# Laser-Battle-IR-Sensor.net
KiCad netlist of a schematic drawn in EAGLE
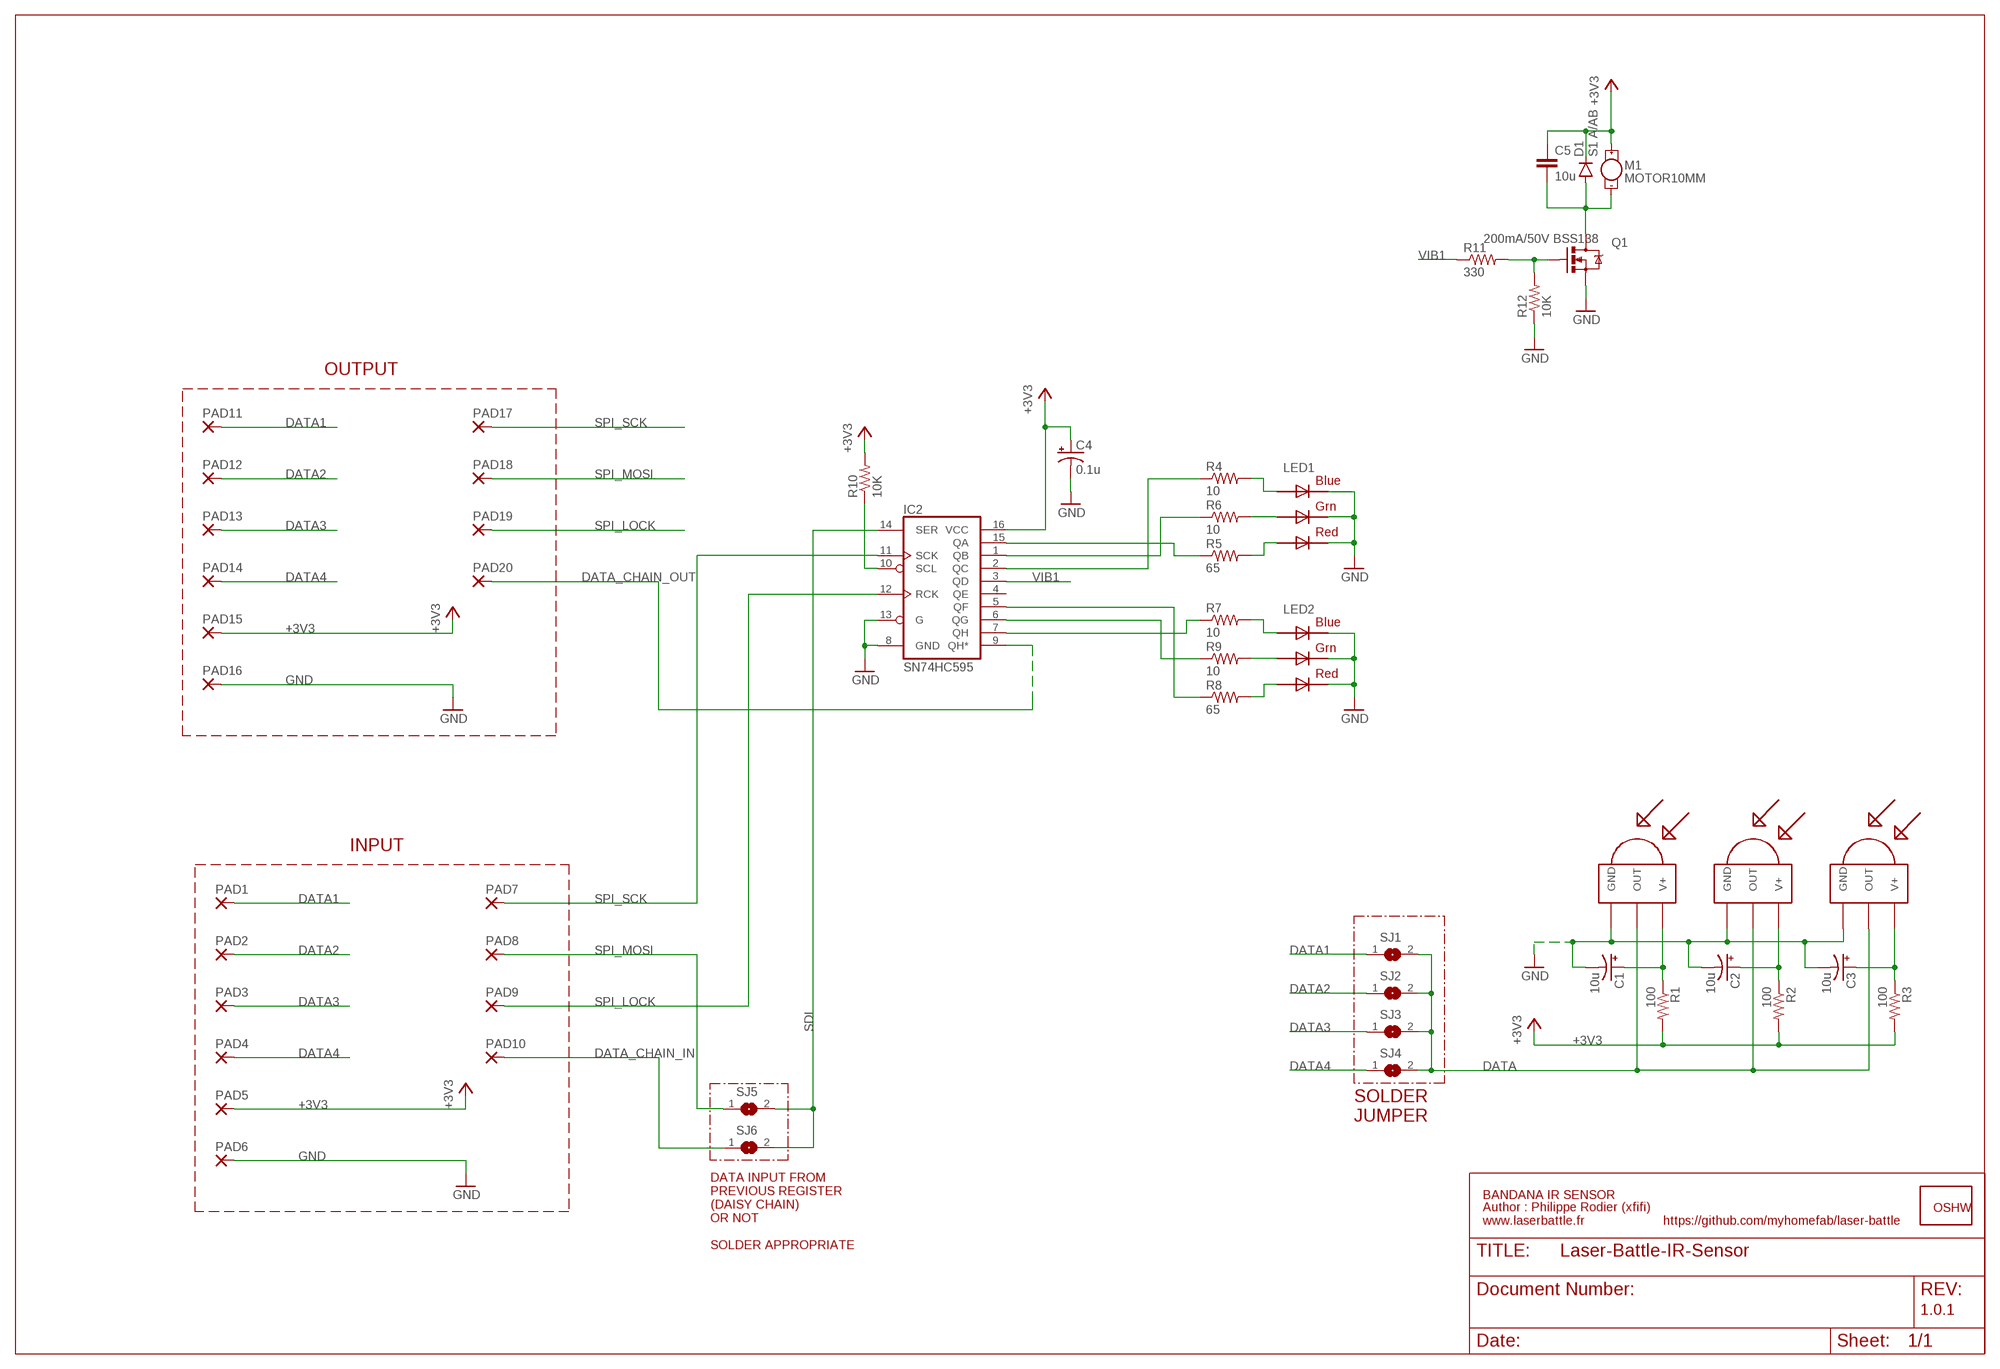
[diagram p0: schematic, sheet 1]

(export (version "E")
  (design (tool "Eeschema 10.0.6"))
  (components
    (comp (ref "C1")
      (value "10u")
      (footprint "eagle-import:EIA3216")
      (libsource (lib "eagle-import") (part "CAP_POL1206"))
    )
    (comp (ref "C2")
      (value "10u")
      (footprint "eagle-import:EIA3216")
      (libsource (lib "eagle-import") (part "CAP_POL1206"))
    )
    (comp (ref "C3")
      (value "10u")
      (footprint "eagle-import:EIA3216")
      (libsource (lib "eagle-import") (part "CAP_POL1206"))
    )
    (comp (ref "C4")
      (value "0.1u")
      (footprint "eagle-import:EIA3216")
      (libsource (lib "eagle-import") (part "CAP_POL1206"))
    )
    (comp (ref "C5")
      (value "10u")
      (footprint "eagle-import:0603-CAP")
      (libsource (lib "eagle-import") (part "CAP0603-CAP"))
    )
    (comp (ref "D1")
      (value "S1 A/AB")
      (footprint "eagle-import:SMA-DIODE")
      (libsource (lib "eagle-import") (part "DIODESMA"))
    )
    (comp (ref "GOLD_ORB_SM1")
      (value "OSHWLOGO_GOLD_ORB_SM")
      (footprint "eagle-import:OSHW2")
      (libsource (lib "eagle-import") (part "OSHWLOGO_GOLD_ORB_SM"))
    )
    (comp (ref "IC2")
      (value "SN74HC595")
      (footprint "eagle-import:TSSOP16")
      (libsource (lib "eagle-import") (part "74595"))
    )
    (comp (ref "IR1")
      (value "TSOP4856")
      (footprint "eagle-import:TSOP18XX")
      (libsource (lib "eagle-import") (part "TSOP4856"))
    )
    (comp (ref "IR2")
      (value "TSOP4856")
      (footprint "eagle-import:TSOP18XX")
      (libsource (lib "eagle-import") (part "TSOP4856"))
    )
    (comp (ref "IR3")
      (value "TSOP4856")
      (footprint "eagle-import:TSOP18XX")
      (libsource (lib "eagle-import") (part "TSOP4856"))
    )
    (comp (ref "LED1")
      (value "RGBLED5050")
      (footprint "eagle-import:RGBLED5050")
      (libsource (lib "eagle-import") (part "RGBLED5050"))
    )
    (comp (ref "LED2")
      (value "RGBLED5050")
      (footprint "eagle-import:RGBLED5050")
      (libsource (lib "eagle-import") (part "RGBLED5050"))
    )
    (comp (ref "M1")
      (value "MOTOR10MM")
      (footprint "eagle-import:VIBE-MOTOR-10MM")
      (libsource (lib "eagle-import") (part "MOTOR10MM"))
    )
    (comp (ref "PAD1")
      (value "1,6/0,8")
      (footprint "eagle-import:1,6_0,8")
      (libsource (lib "eagle-import") (part "1,6/0,8"))
    )
    (comp (ref "PAD2")
      (value "1,6/0,8")
      (footprint "eagle-import:1,6_0,8")
      (libsource (lib "eagle-import") (part "1,6/0,8"))
    )
    (comp (ref "PAD3")
      (value "1,6/0,8")
      (footprint "eagle-import:1,6_0,8")
      (libsource (lib "eagle-import") (part "1,6/0,8"))
    )
    (comp (ref "PAD4")
      (value "1,6/0,8")
      (footprint "eagle-import:1,6_0,8")
      (libsource (lib "eagle-import") (part "1,6/0,8"))
    )
    (comp (ref "PAD5")
      (value "1,6/0,8")
      (footprint "eagle-import:1,6_0,8")
      (libsource (lib "eagle-import") (part "1,6/0,8"))
    )
    (comp (ref "PAD6")
      (value "1,6/0,8")
      (footprint "eagle-import:1,6_0,8")
      (libsource (lib "eagle-import") (part "1,6/0,8"))
    )
    (comp (ref "PAD7")
      (value "1,6/0,8")
      (footprint "eagle-import:1,6_0,8")
      (libsource (lib "eagle-import") (part "1,6/0,8"))
    )
    (comp (ref "PAD8")
      (value "1,6/0,8")
      (footprint "eagle-import:1,6_0,8")
      (libsource (lib "eagle-import") (part "1,6/0,8"))
    )
    (comp (ref "PAD9")
      (value "1,6/0,8")
      (footprint "eagle-import:1,6_0,8")
      (libsource (lib "eagle-import") (part "1,6/0,8"))
    )
    (comp (ref "PAD10")
      (value "1,6/0,8")
      (footprint "eagle-import:1,6_0,8")
      (libsource (lib "eagle-import") (part "1,6/0,8"))
    )
    (comp (ref "PAD11")
      (value "1,6/0,8")
      (footprint "eagle-import:1,6_0,8")
      (libsource (lib "eagle-import") (part "1,6/0,8"))
    )
    (comp (ref "PAD12")
      (value "1,6/0,8")
      (footprint "eagle-import:1,6_0,8")
      (libsource (lib "eagle-import") (part "1,6/0,8"))
    )
    (comp (ref "PAD13")
      (value "1,6/0,8")
      (footprint "eagle-import:1,6_0,8")
      (libsource (lib "eagle-import") (part "1,6/0,8"))
    )
    (comp (ref "PAD14")
      (value "1,6/0,8")
      (footprint "eagle-import:1,6_0,8")
      (libsource (lib "eagle-import") (part "1,6/0,8"))
    )
    (comp (ref "PAD15")
      (value "1,6/0,8")
      (footprint "eagle-import:1,6_0,8")
      (libsource (lib "eagle-import") (part "1,6/0,8"))
    )
    (comp (ref "PAD16")
      (value "1,6/0,8")
      (footprint "eagle-import:1,6_0,8")
      (libsource (lib "eagle-import") (part "1,6/0,8"))
    )
    (comp (ref "PAD17")
      (value "1,6/0,8")
      (footprint "eagle-import:1,6_0,8")
      (libsource (lib "eagle-import") (part "1,6/0,8"))
    )
    (comp (ref "PAD18")
      (value "1,6/0,8")
      (footprint "eagle-import:1,6_0,8")
      (libsource (lib "eagle-import") (part "1,6/0,8"))
    )
    (comp (ref "PAD19")
      (value "1,6/0,8")
      (footprint "eagle-import:1,6_0,8")
      (libsource (lib "eagle-import") (part "1,6/0,8"))
    )
    (comp (ref "PAD20")
      (value "1,6/0,8")
      (footprint "eagle-import:1,6_0,8")
      (libsource (lib "eagle-import") (part "1,6/0,8"))
    )
    (comp (ref "Q1")
      (value "200mA/50V BSS138")
      (footprint "eagle-import:SOT23-3")
      (libsource (lib "eagle-import") (part "MOSFET-NCHANNELBSS138"))
    )
    (comp (ref "R1")
      (value "100")
      (footprint "eagle-import:0603-RES")
      (libsource (lib "eagle-import") (part "100OHM-1/10W-1%(0603)"))
    )
    (comp (ref "R2")
      (value "100")
      (footprint "eagle-import:0603-RES")
      (libsource (lib "eagle-import") (part "100OHM-1/10W-1%(0603)"))
    )
    (comp (ref "R3")
      (value "100")
      (footprint "eagle-import:0603-RES")
      (libsource (lib "eagle-import") (part "100OHM-1/10W-1%(0603)"))
    )
    (comp (ref "R4")
      (value "10")
      (footprint "eagle-import:0603-RES")
      (libsource (lib "eagle-import") (part "3.3KOHM1/10W1%(0603)"))
    )
    (comp (ref "R5")
      (value "65")
      (footprint "eagle-import:0603-RES")
      (libsource (lib "eagle-import") (part "3.3KOHM1/10W1%(0603)"))
    )
    (comp (ref "R6")
      (value "10")
      (footprint "eagle-import:0603-RES")
      (libsource (lib "eagle-import") (part "3.3KOHM1/10W1%(0603)"))
    )
    (comp (ref "R7")
      (value "10")
      (footprint "eagle-import:0603-RES")
      (libsource (lib "eagle-import") (part "3.3KOHM1/10W1%(0603)"))
    )
    (comp (ref "R8")
      (value "65")
      (footprint "eagle-import:0603-RES")
      (libsource (lib "eagle-import") (part "3.3KOHM1/10W1%(0603)"))
    )
    (comp (ref "R9")
      (value "10")
      (footprint "eagle-import:0603-RES")
      (libsource (lib "eagle-import") (part "3.3KOHM1/10W1%(0603)"))
    )
    (comp (ref "R10")
      (value "10K")
      (footprint "eagle-import:0603-RES")
      (libsource (lib "eagle-import") (part "10KOHM-1/10W-1%(0603)0603"))
    )
    (comp (ref "R11")
      (value "330")
      (footprint "eagle-import:0603-RES")
      (libsource (lib "eagle-import") (part "330OHM1/10W1%(0603)"))
    )
    (comp (ref "R12")
      (value "10K")
      (footprint "eagle-import:0603-RES")
      (libsource (lib "eagle-import") (part "10KOHM-1/10W-1%(0603)0603"))
    )
    (comp (ref "SJ1") (value "SJ") (footprint "eagle-import:SJ") (libsource (lib "eagle-import") (part "SJ")))
    (comp (ref "SJ2") (value "SJ") (footprint "eagle-import:SJ") (libsource (lib "eagle-import") (part "SJ")))
    (comp (ref "SJ3") (value "SJ") (footprint "eagle-import:SJ") (libsource (lib "eagle-import") (part "SJ")))
    (comp (ref "SJ4") (value "SJ") (footprint "eagle-import:SJ") (libsource (lib "eagle-import") (part "SJ")))
    (comp (ref "SJ5") (value "SJ") (footprint "eagle-import:SJ") (libsource (lib "eagle-import") (part "SJ")))
    (comp (ref "SJ6") (value "SJ") (footprint "eagle-import:SJ") (libsource (lib "eagle-import") (part "SJ")))
  )
  (nets
    (net (code "1") (name "+3V3") (class "Default")
      (node (ref "C4") (pin "A") (pinfunction "+_A") (pintype "passive"))
      (node (ref "C5") (pin "1") (pinfunction "1_1") (pintype "passive"))
      (node (ref "D1") (pin "C") (pinfunction "C_C") (pintype "passive"))
      (node (ref "IC2") (pin "16") (pinfunction "VCC_16") (pintype "power_in"))
      (node (ref "M1") (pin "+") (pinfunction "+_+") (pintype "bidirectional"))
      (node (ref "PAD15") (pin "1") (pinfunction "P_1") (pintype "passive"))
      (node (ref "PAD5") (pin "1") (pinfunction "P_1") (pintype "passive"))
      (node (ref "R1") (pin "2") (pinfunction "2_2") (pintype "passive"))
      (node (ref "R10") (pin "2") (pinfunction "2_2") (pintype "passive"))
      (node (ref "R2") (pin "2") (pinfunction "2_2") (pintype "passive"))
      (node (ref "R3") (pin "2") (pinfunction "2_2") (pintype "passive"))
    )
    (net (code "2") (name "/DATA") (class "Default")
      (node (ref "IR1") (pin "OUT") (pinfunction "OUT_OUT") (pintype "bidirectional"))
      (node (ref "IR2") (pin "OUT") (pinfunction "OUT_OUT") (pintype "bidirectional"))
      (node (ref "IR3") (pin "OUT") (pinfunction "OUT_OUT") (pintype "bidirectional"))
      (node (ref "SJ1") (pin "2") (pinfunction "2_2") (pintype "passive"))
      (node (ref "SJ2") (pin "2") (pinfunction "2_2") (pintype "passive"))
      (node (ref "SJ3") (pin "2") (pinfunction "2_2") (pintype "passive"))
      (node (ref "SJ4") (pin "2") (pinfunction "2_2") (pintype "passive"))
    )
    (net (code "3") (name "/DATA1") (class "Default")
      (node (ref "PAD1") (pin "1") (pinfunction "P_1") (pintype "passive"))
      (node (ref "PAD11") (pin "1") (pinfunction "P_1") (pintype "passive"))
      (node (ref "SJ1") (pin "1") (pinfunction "1_1") (pintype "passive"))
    )
    (net (code "4") (name "/DATA2") (class "Default")
      (node (ref "PAD12") (pin "1") (pinfunction "P_1") (pintype "passive"))
      (node (ref "PAD2") (pin "1") (pinfunction "P_1") (pintype "passive"))
      (node (ref "SJ2") (pin "1") (pinfunction "1_1") (pintype "passive"))
    )
    (net (code "5") (name "/DATA3") (class "Default")
      (node (ref "PAD13") (pin "1") (pinfunction "P_1") (pintype "passive"))
      (node (ref "PAD3") (pin "1") (pinfunction "P_1") (pintype "passive"))
      (node (ref "SJ3") (pin "1") (pinfunction "1_1") (pintype "passive"))
    )
    (net (code "6") (name "/DATA4") (class "Default")
      (node (ref "PAD14") (pin "1") (pinfunction "P_1") (pintype "passive"))
      (node (ref "PAD4") (pin "1") (pinfunction "P_1") (pintype "passive"))
      (node (ref "SJ4") (pin "1") (pinfunction "1_1") (pintype "passive"))
    )
    (net (code "7") (name "/DATA_CHAIN_IN") (class "Default")
      (node (ref "PAD10") (pin "1") (pinfunction "P_1") (pintype "passive"))
      (node (ref "SJ6") (pin "1") (pinfunction "1_1") (pintype "passive"))
    )
    (net (code "8") (name "/DATA_CHAIN_OUT") (class "Default")
      (node (ref "IC2") (pin "9") (pinfunction "QH*_9") (pintype "tri_state"))
      (node (ref "PAD20") (pin "1") (pinfunction "P_1") (pintype "passive"))
    )
    (net (code "9") (name "/SDI") (class "Default")
      (node (ref "IC2") (pin "14") (pinfunction "SER_14") (pintype "input"))
      (node (ref "SJ5") (pin "2") (pinfunction "2_2") (pintype "passive"))
      (node (ref "SJ6") (pin "2") (pinfunction "2_2") (pintype "passive"))
    )
    (net (code "10") (name "/SPI_LOCK") (class "Default")
      (node (ref "IC2") (pin "12") (pinfunction "RCK_12") (pintype "input"))
      (node (ref "PAD19") (pin "1") (pinfunction "P_1") (pintype "passive"))
      (node (ref "PAD9") (pin "1") (pinfunction "P_1") (pintype "passive"))
    )
    (net (code "11") (name "/SPI_MOSI") (class "Default")
      (node (ref "PAD18") (pin "1") (pinfunction "P_1") (pintype "passive"))
      (node (ref "PAD8") (pin "1") (pinfunction "P_1") (pintype "passive"))
      (node (ref "SJ5") (pin "1") (pinfunction "1_1") (pintype "passive"))
    )
    (net (code "12") (name "/SPI_SCK") (class "Default")
      (node (ref "IC2") (pin "11") (pinfunction "SCK_11") (pintype "input"))
      (node (ref "PAD17") (pin "1") (pinfunction "P_1") (pintype "passive"))
      (node (ref "PAD7") (pin "1") (pinfunction "P_1") (pintype "passive"))
    )
    (net (code "13") (name "/VIB1") (class "Default")
      (node (ref "IC2") (pin "3") (pinfunction "QD_3") (pintype "tri_state"))
      (node (ref "R11") (pin "1") (pinfunction "1_1") (pintype "passive"))
    )
    (net (code "14") (name "GND") (class "Default")
      (node (ref "C1") (pin "C") (pinfunction "-_C") (pintype "passive"))
      (node (ref "C2") (pin "C") (pinfunction "-_C") (pintype "passive"))
      (node (ref "C3") (pin "C") (pinfunction "-_C") (pintype "passive"))
      (node (ref "C4") (pin "C") (pinfunction "-_C") (pintype "passive"))
      (node (ref "IC2") (pin "13") (pinfunction "G_13") (pintype "input"))
      (node (ref "IC2") (pin "8") (pinfunction "GND_8") (pintype "power_in"))
      (node (ref "IR1") (pin "GND") (pinfunction "GND_GND") (pintype "bidirectional"))
      (node (ref "IR2") (pin "GND") (pinfunction "GND_GND") (pintype "bidirectional"))
      (node (ref "IR3") (pin "GND") (pinfunction "GND_GND") (pintype "bidirectional"))
      (node (ref "LED1") (pin "4") (pinfunction "BLUE_C_4") (pintype "bidirectional"))
      (node (ref "LED1") (pin "5") (pinfunction "RED_C_5") (pintype "bidirectional"))
      (node (ref "LED1") (pin "6") (pinfunction "GREEN_C_6") (pintype "bidirectional"))
      (node (ref "LED2") (pin "4") (pinfunction "BLUE_C_4") (pintype "bidirectional"))
      (node (ref "LED2") (pin "5") (pinfunction "RED_C_5") (pintype "bidirectional"))
      (node (ref "LED2") (pin "6") (pinfunction "GREEN_C_6") (pintype "bidirectional"))
      (node (ref "PAD16") (pin "1") (pinfunction "P_1") (pintype "passive"))
      (node (ref "PAD6") (pin "1") (pinfunction "P_1") (pintype "passive"))
      (node (ref "Q1") (pin "2") (pinfunction "S_2") (pintype "passive"))
      (node (ref "R12") (pin "1") (pinfunction "1_1") (pintype "passive"))
    )
    (net (code "15") (name "Net-(C1-+)") (class "Default")
      (node (ref "C1") (pin "A") (pinfunction "+_A") (pintype "passive"))
      (node (ref "IR1") (pin "VCC") (pinfunction "V+_VCC") (pintype "bidirectional"))
      (node (ref "R1") (pin "1") (pinfunction "1_1") (pintype "passive"))
    )
    (net (code "16") (name "Net-(C2-+)") (class "Default")
      (node (ref "C2") (pin "A") (pinfunction "+_A") (pintype "passive"))
      (node (ref "IR2") (pin "VCC") (pinfunction "V+_VCC") (pintype "bidirectional"))
      (node (ref "R2") (pin "1") (pinfunction "1_1") (pintype "passive"))
    )
    (net (code "17") (name "Net-(C3-+)") (class "Default")
      (node (ref "C3") (pin "A") (pinfunction "+_A") (pintype "passive"))
      (node (ref "IR3") (pin "VCC") (pinfunction "V+_VCC") (pintype "bidirectional"))
      (node (ref "R3") (pin "1") (pinfunction "1_1") (pintype "passive"))
    )
    (net (code "18") (name "Net-(IC2-QA)") (class "Default")
      (node (ref "IC2") (pin "15") (pinfunction "QA_15") (pintype "tri_state"))
      (node (ref "R5") (pin "1") (pinfunction "1_1") (pintype "passive"))
    )
    (net (code "19") (name "Net-(IC2-QB)") (class "Default")
      (node (ref "IC2") (pin "1") (pinfunction "QB_1") (pintype "tri_state"))
      (node (ref "R6") (pin "1") (pinfunction "1_1") (pintype "passive"))
    )
    (net (code "20") (name "Net-(IC2-QC)") (class "Default")
      (node (ref "IC2") (pin "2") (pinfunction "QC_2") (pintype "tri_state"))
      (node (ref "R4") (pin "1") (pinfunction "1_1") (pintype "passive"))
    )
    (net (code "21") (name "Net-(IC2-QF)") (class "Default")
      (node (ref "IC2") (pin "5") (pinfunction "QF_5") (pintype "tri_state"))
      (node (ref "R8") (pin "1") (pinfunction "1_1") (pintype "passive"))
    )
    (net (code "22") (name "Net-(IC2-QG)") (class "Default")
      (node (ref "IC2") (pin "6") (pinfunction "QG_6") (pintype "tri_state"))
      (node (ref "R9") (pin "1") (pinfunction "1_1") (pintype "passive"))
    )
    (net (code "23") (name "Net-(IC2-QH)") (class "Default")
      (node (ref "IC2") (pin "7") (pinfunction "QH_7") (pintype "tri_state"))
      (node (ref "R7") (pin "1") (pinfunction "1_1") (pintype "passive"))
    )
    (net (code "24") (name "Net-(IC2-SCL)") (class "Default")
      (node (ref "IC2") (pin "10") (pinfunction "SCL_10") (pintype "input"))
      (node (ref "R10") (pin "1") (pinfunction "1_1") (pintype "passive"))
    )
    (net (code "25") (name "Net-(LED1-BLUE_A)") (class "Default")
      (node (ref "LED1") (pin "3") (pinfunction "BLUE_A_3") (pintype "bidirectional"))
      (node (ref "R4") (pin "2") (pinfunction "2_2") (pintype "passive"))
    )
    (net (code "26") (name "Net-(LED1-GREEN_A)") (class "Default")
      (node (ref "LED1") (pin "1") (pinfunction "GREEN_A_1") (pintype "bidirectional"))
      (node (ref "R6") (pin "2") (pinfunction "2_2") (pintype "passive"))
    )
    (net (code "27") (name "Net-(LED1-RED_A)") (class "Default")
      (node (ref "LED1") (pin "2") (pinfunction "RED_A_2") (pintype "bidirectional"))
      (node (ref "R5") (pin "2") (pinfunction "2_2") (pintype "passive"))
    )
    (net (code "28") (name "Net-(LED2-BLUE_A)") (class "Default")
      (node (ref "LED2") (pin "3") (pinfunction "BLUE_A_3") (pintype "bidirectional"))
      (node (ref "R7") (pin "2") (pinfunction "2_2") (pintype "passive"))
    )
    (net (code "29") (name "Net-(LED2-GREEN_A)") (class "Default")
      (node (ref "LED2") (pin "1") (pinfunction "GREEN_A_1") (pintype "bidirectional"))
      (node (ref "R9") (pin "2") (pinfunction "2_2") (pintype "passive"))
    )
    (net (code "30") (name "Net-(LED2-RED_A)") (class "Default")
      (node (ref "LED2") (pin "2") (pinfunction "RED_A_2") (pintype "bidirectional"))
      (node (ref "R8") (pin "2") (pinfunction "2_2") (pintype "passive"))
    )
    (net (code "31") (name "Net-(Q1-D)") (class "Default")
      (node (ref "C5") (pin "2") (pinfunction "2_2") (pintype "passive"))
      (node (ref "D1") (pin "A") (pinfunction "A_A") (pintype "passive"))
      (node (ref "M1") (pin "-") (pinfunction "-_-") (pintype "bidirectional"))
      (node (ref "Q1") (pin "3") (pinfunction "D_3") (pintype "passive"))
    )
    (net (code "32") (name "Net-(Q1-G)") (class "Default")
      (node (ref "Q1") (pin "1") (pinfunction "G_1") (pintype "passive"))
      (node (ref "R11") (pin "2") (pinfunction "2_2") (pintype "passive"))
      (node (ref "R12") (pin "2") (pinfunction "2_2") (pintype "passive"))
    )
    (net (code "33") (name "unconnected-(IC2-QE-Pad4)") (class "Default")
      (node (ref "IC2") (pin "4") (pinfunction "QE_4") (pintype "tri_state"))
    )
  )
)
